# SAIIoT2020_AccelKart.net
KiCad netlist of a schematic drawn in EasyEDA
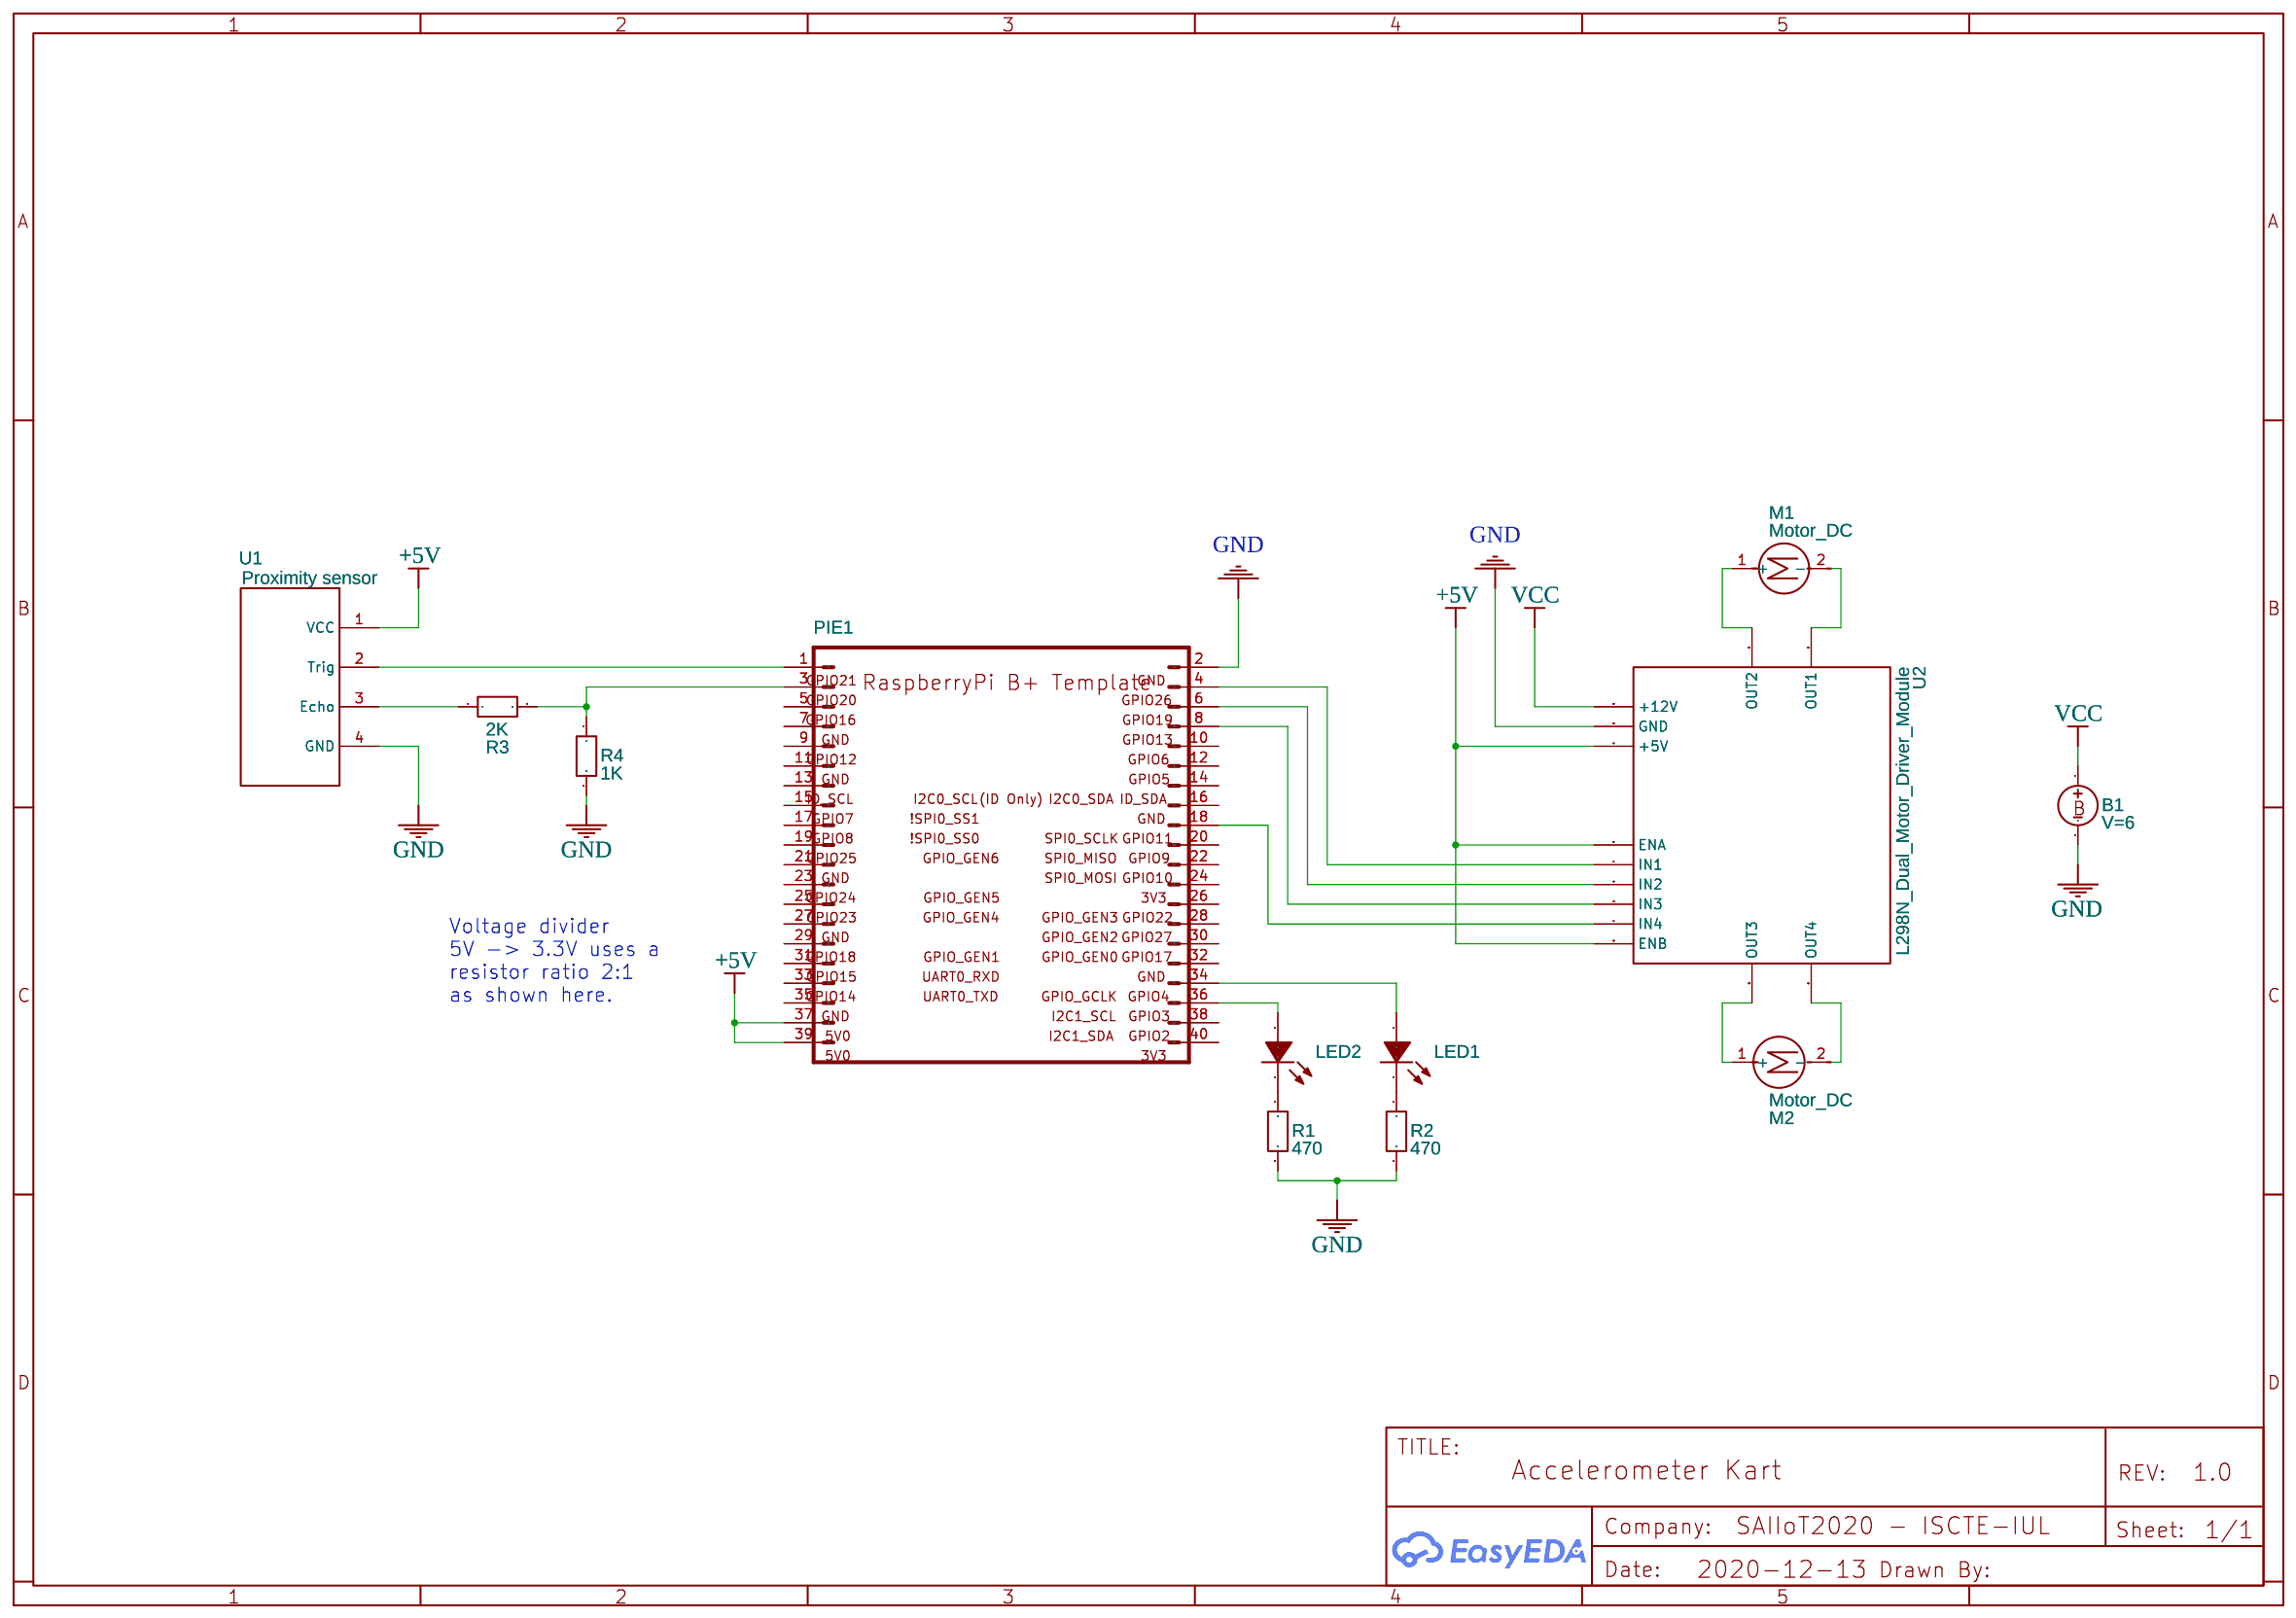
[diagram p0: Kart]
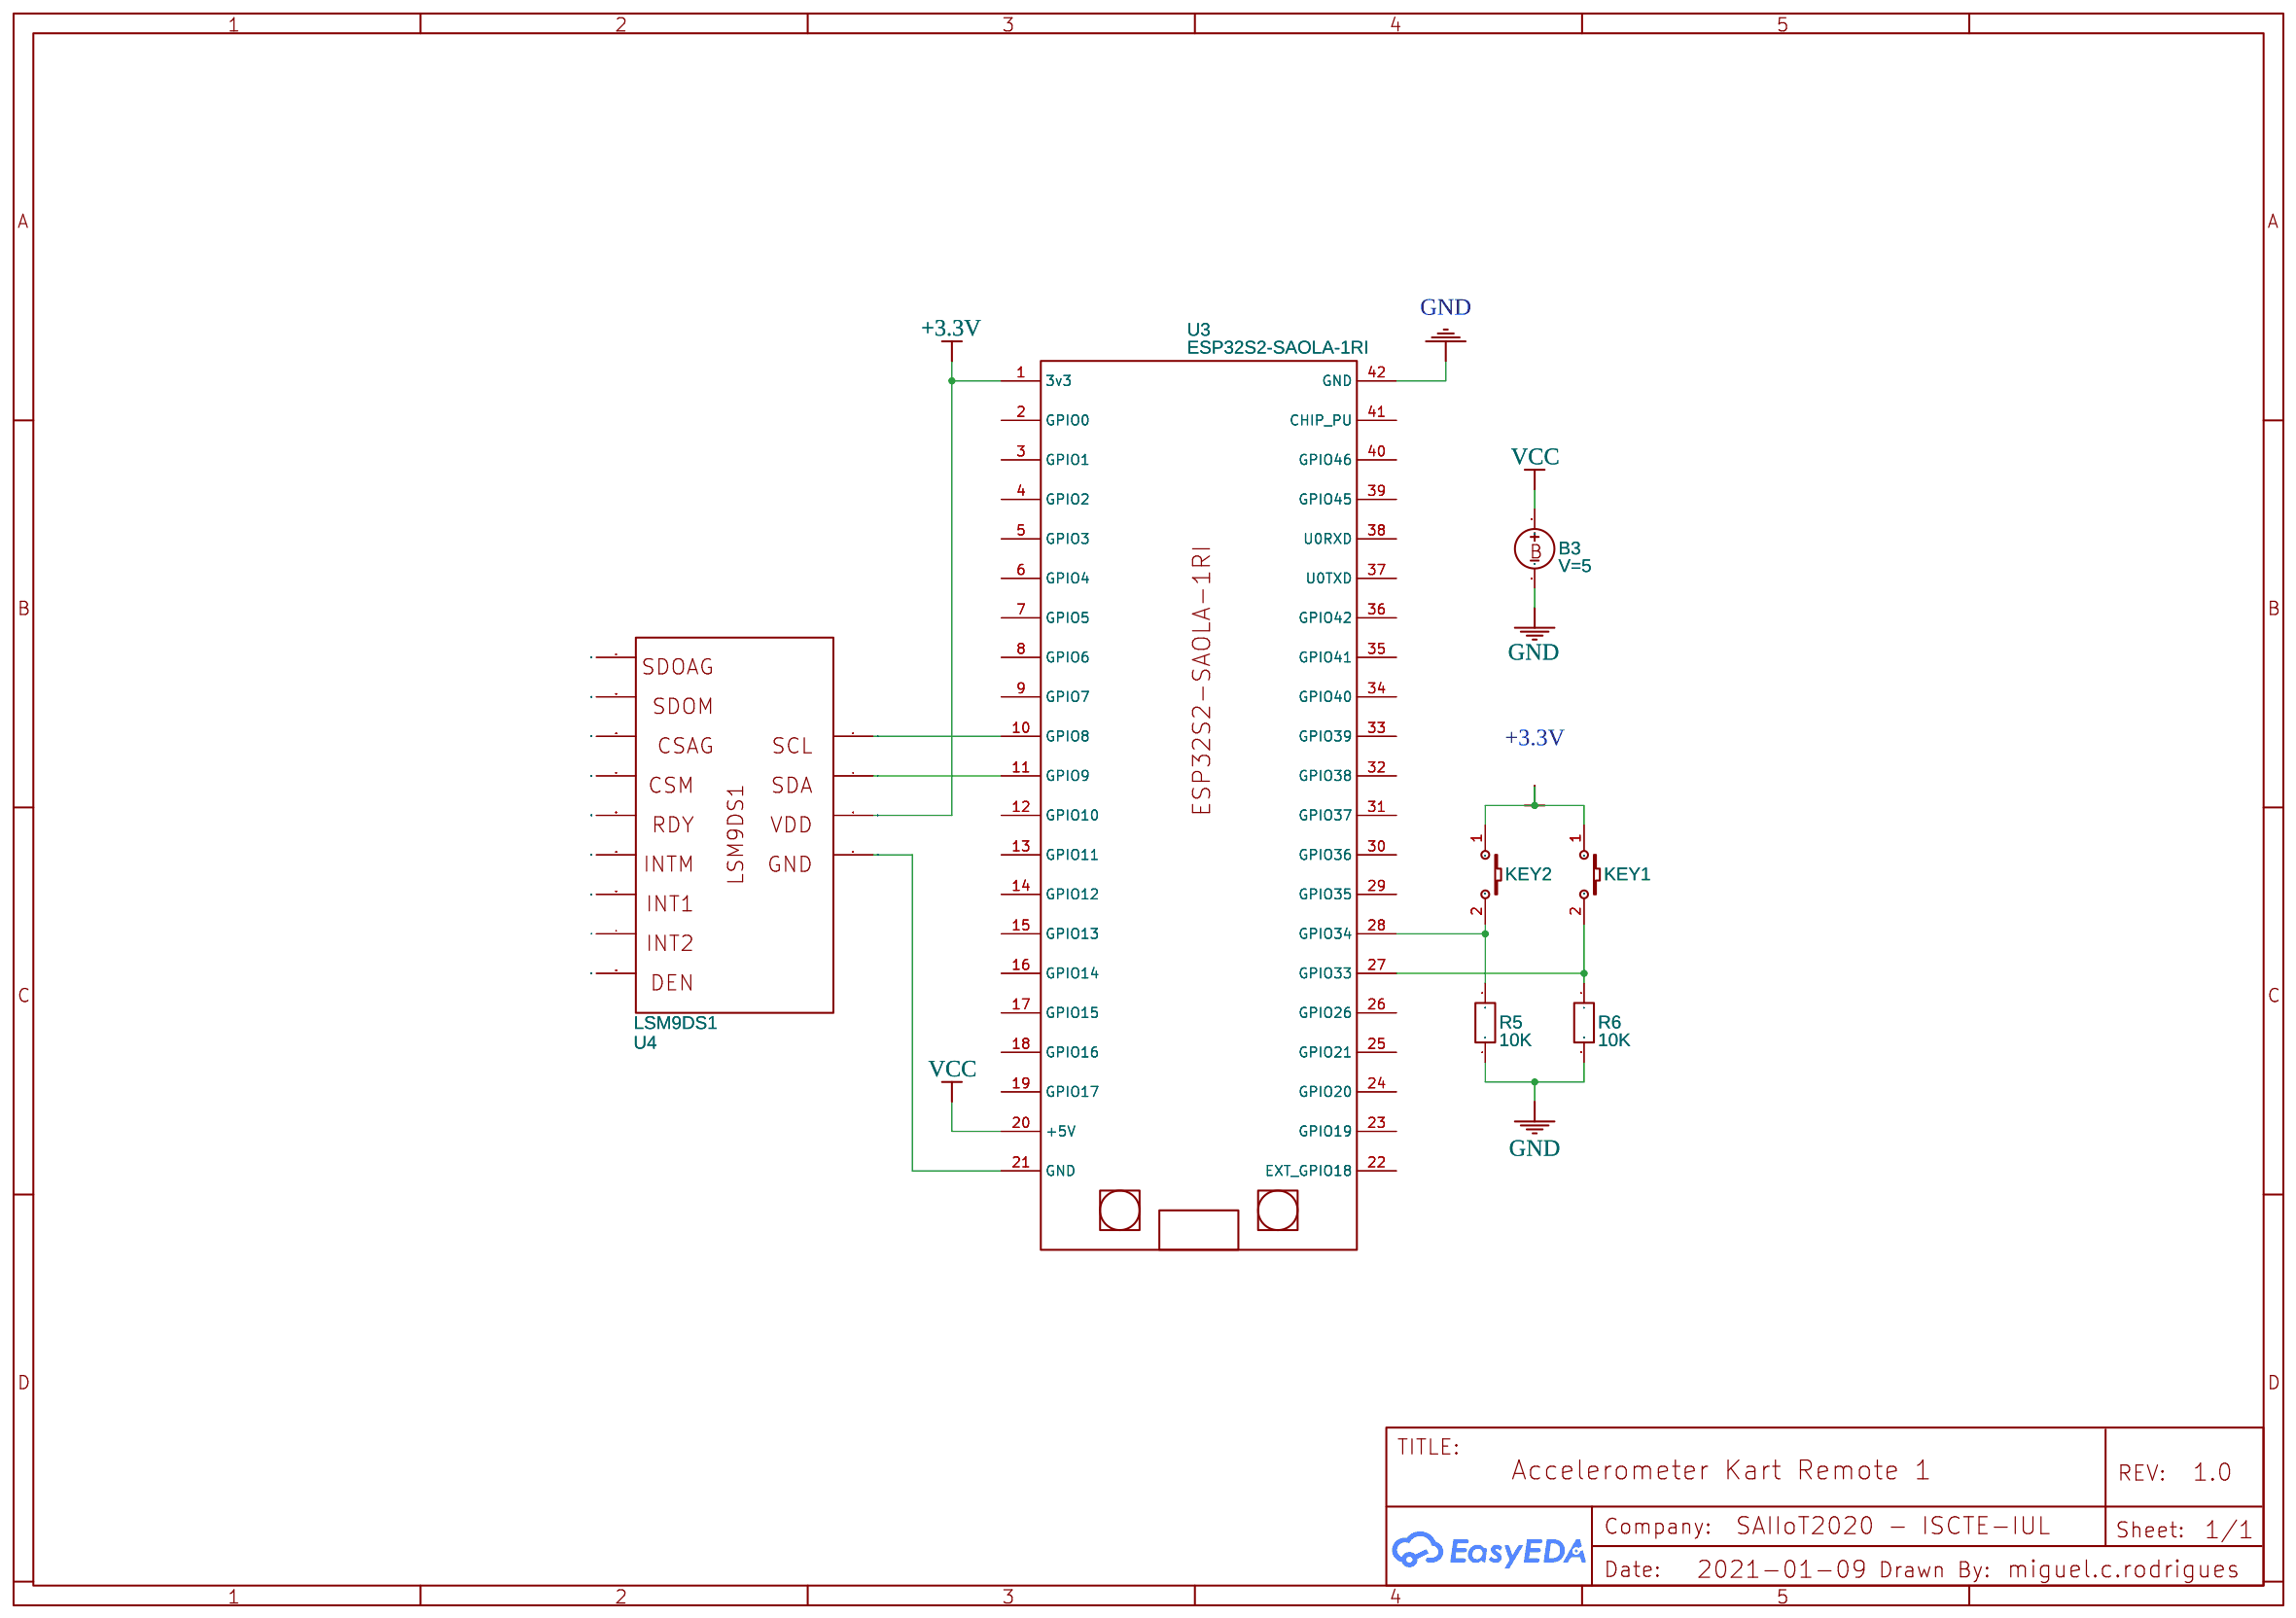
[diagram p1: Remote 1]
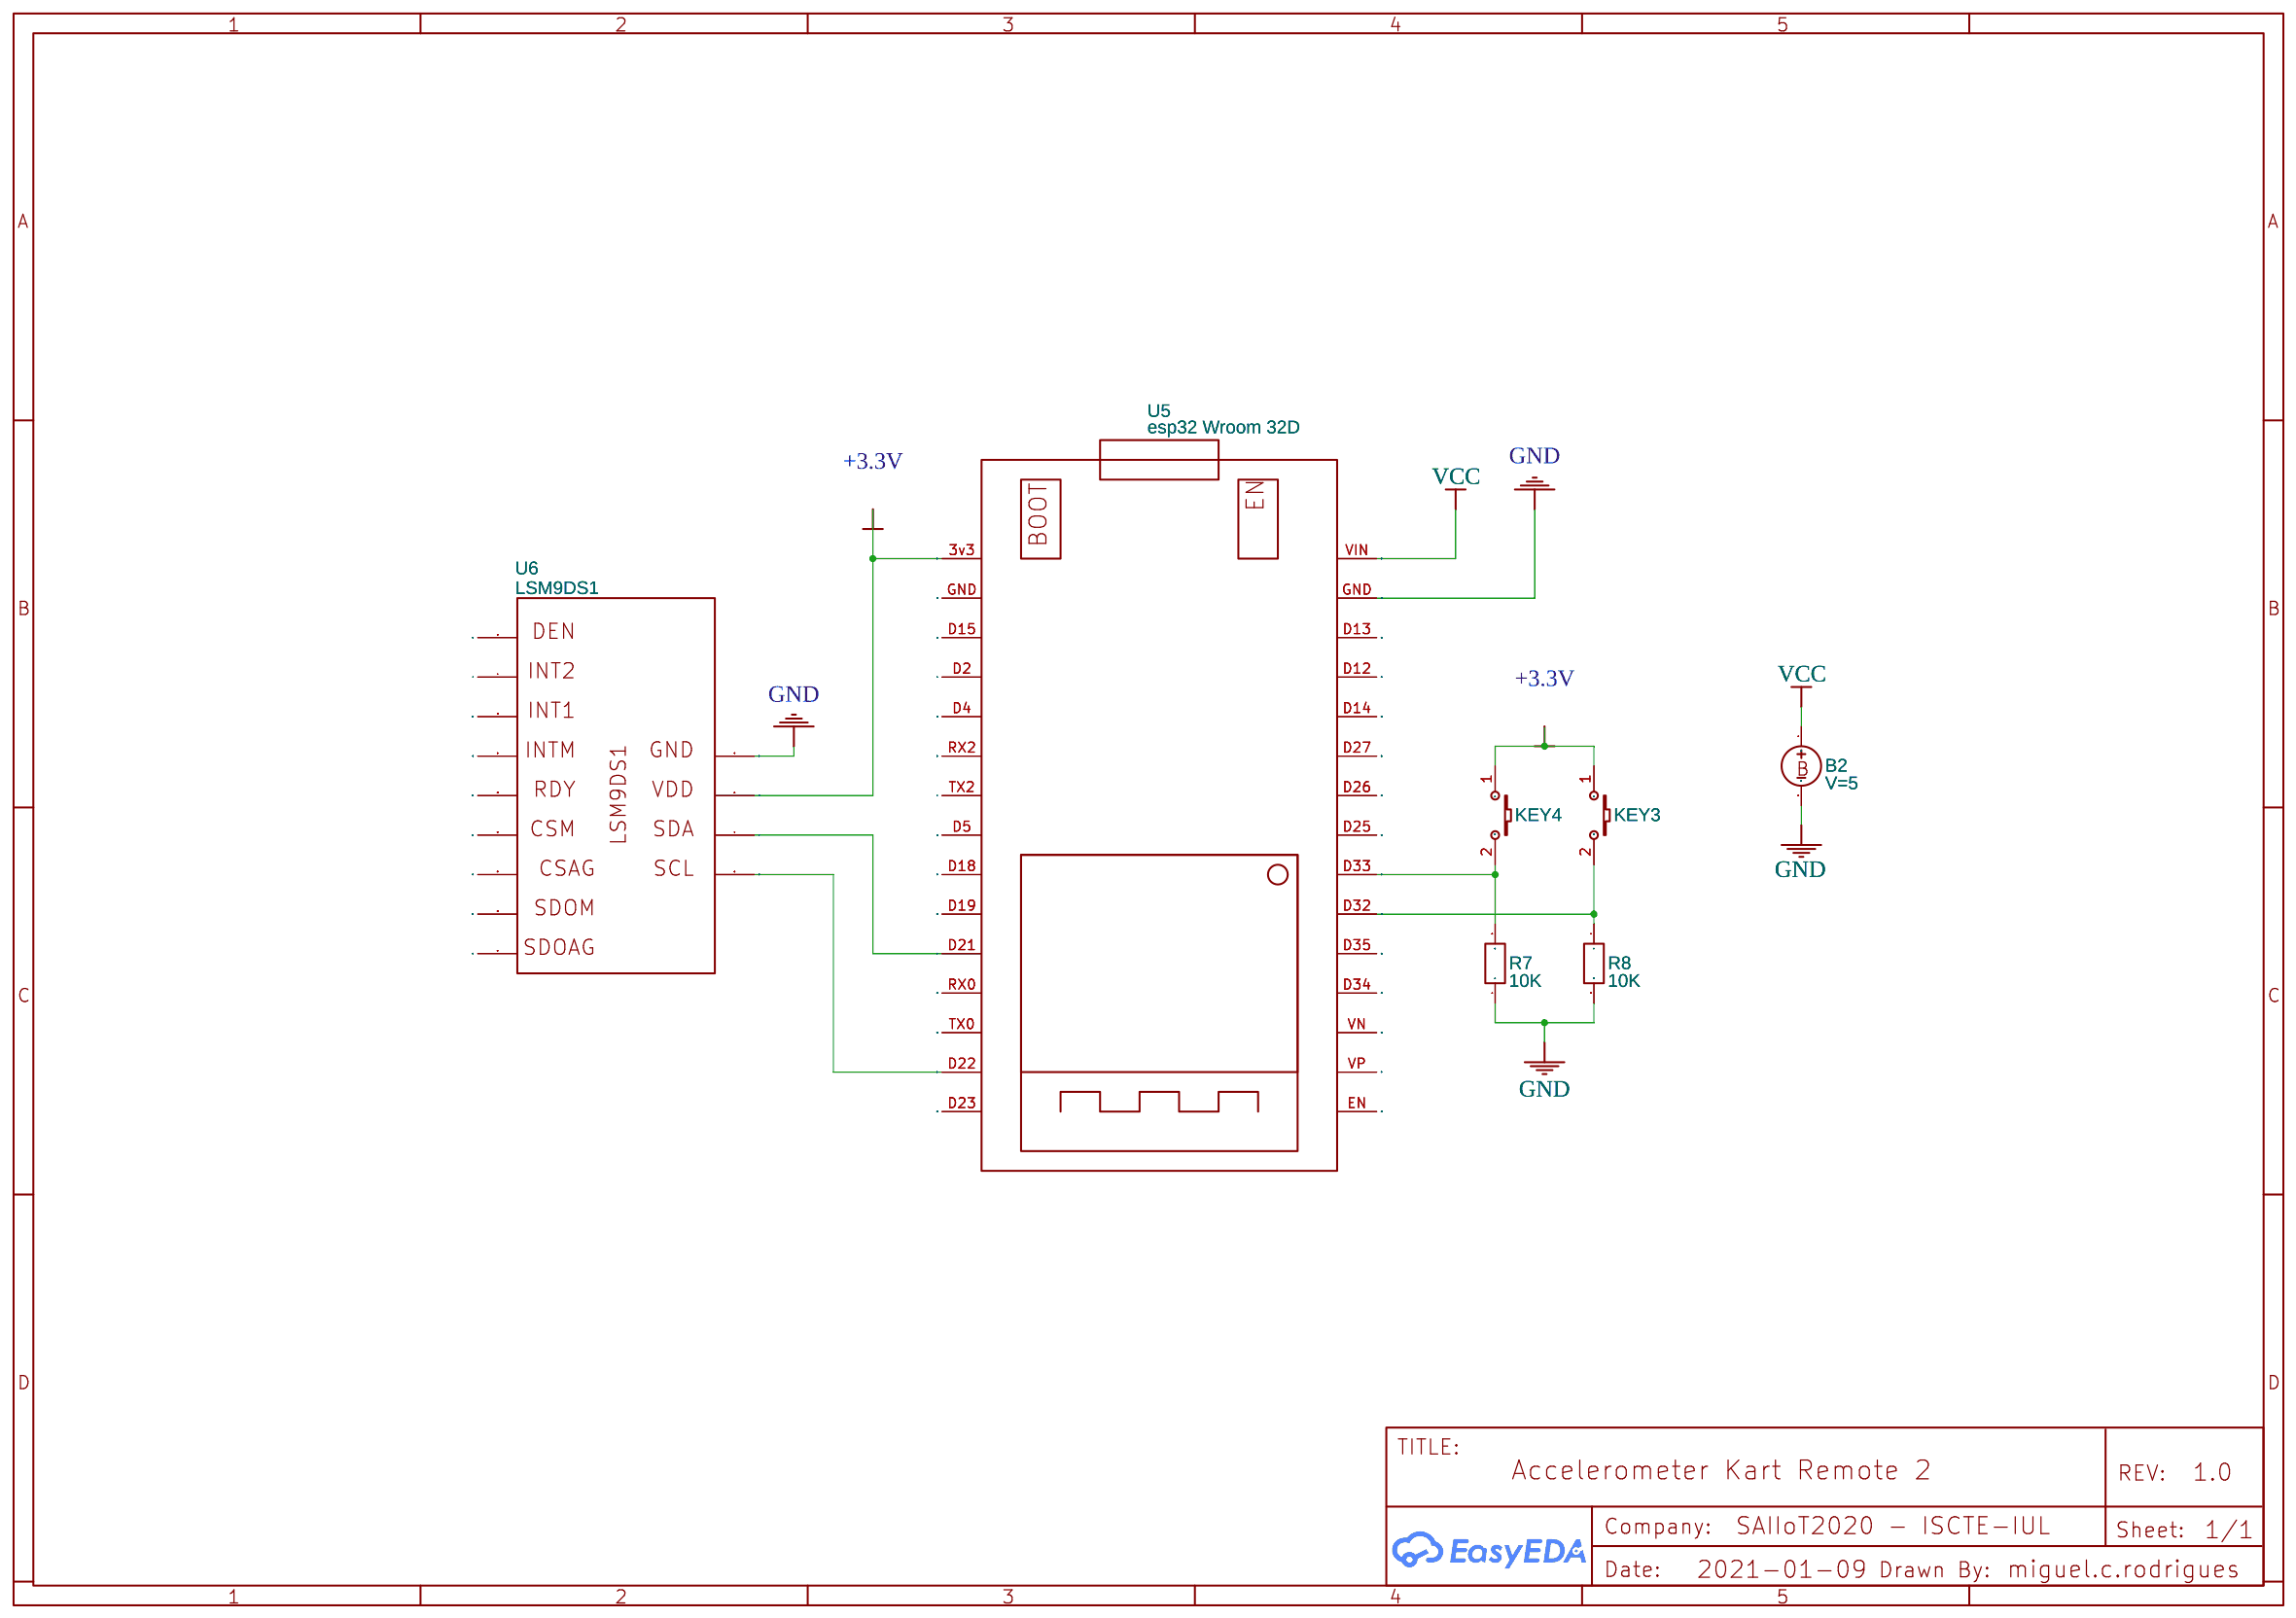
[diagram p2: Remote 2]

(export (version "E")
  (design (tool "Eeschema 10.0.6"))
  (components
    (comp (ref "B1") (value "V=6") (libsource (lib "") (part "BV_Behavioral_Source")))
    (comp (ref "LED1")
      (value "LED-0603_R")
      (fields
        (field (name "BOM_Manufacturer Part") "19-217/R6C-AL1M2VY/3T")
        (field (name "BOM_Supplier Part") "C72044")
      )
      (libsource (lib "") (part "LED-0603_R"))
    )
    (comp (ref "LED2")
      (value "LED-0603_R")
      (fields
        (field (name "BOM_Manufacturer Part") "19-217/R6C-AL1M2VY/3T")
        (field (name "BOM_Supplier Part") "C72044")
      )
      (libsource (lib "") (part "LED-0603_R"))
    )
    (comp (ref "M1") (value "Motor_DC") (libsource (lib "") (part "Motor_DC_1")))
    (comp (ref "M2") (value "Motor_DC") (libsource (lib "") (part "Motor_DC")))
    (comp (ref "PIE1") (value "PA_RASPI_BPLUS_BRD") (libsource (lib "") (part "PA_RASPI_BPLUS_BRD")))
    (comp (ref "R1") (value "470") (libsource (lib "") (part "R_0603_EU")))
    (comp (ref "R2") (value "470") (libsource (lib "") (part "R_0603_EU")))
    (comp (ref "R3") (value "2K") (libsource (lib "") (part "R_0603_EU_1")))
    (comp (ref "R4") (value "1K") (libsource (lib "") (part "R_0603_EU")))
    (comp (ref "U1")
      (value "Proximity sensor")
      (fields (field (name "BOM_Manufacturer Part") "HC-SR04"))
      (libsource (lib "") (part "Proximity sensor"))
    )
    (comp (ref "U2")
      (value "L298N_Dual_Motor_Driver_Module")
      (libsource (lib "") (part "L298N_Dual_Motor_Driver_Module"))
    )
    (comp (ref "B3") (value "V=5") (libsource (lib "") (part "BV_Behavioral_Source")))
    (comp (ref "KEY1")
      (value "K2-3.6×6.1_SMD")
      (fields
        (field (name "BOM_Manufacturer Part") "K2-1107ST-A4SW-06")
        (field (name "BOM_Supplier Part") "C118141")
      )
      (libsource (lib "") (part "K2-3.6×6.1_SMD"))
    )
    (comp (ref "KEY2")
      (value "K2-3.6×6.1_SMD")
      (fields
        (field (name "BOM_Manufacturer Part") "K2-1107ST-A4SW-06")
        (field (name "BOM_Supplier Part") "C118141")
      )
      (libsource (lib "") (part "K2-3.6×6.1_SMD"))
    )
    (comp (ref "R5") (value "10K") (libsource (lib "") (part "R_0603_EU")))
    (comp (ref "R6") (value "10K") (libsource (lib "") (part "R_0603_EU_1")))
    (comp (ref "U3")
      (value "ESP32S2-SAOLA-1RI")
      (fields (field (name "BOM_Manufacturer Part") "ESP32 DEV KIT"))
      (libsource (lib "") (part "ESP32S2-SAOLA-1RI"))
    )
    (comp (ref "U4") (value "LSM9DS1") (libsource (lib "") (part "LSM9DS1")))
    (comp (ref "B2") (value "V=5") (libsource (lib "") (part "BV_Behavioral_Source")))
    (comp (ref "KEY3")
      (value "K2-3.6×6.1_SMD")
      (fields
        (field (name "BOM_Manufacturer Part") "K2-1107ST-A4SW-06")
        (field (name "BOM_Supplier Part") "C118141")
      )
      (libsource (lib "") (part "K2-3.6×6.1_SMD"))
    )
    (comp (ref "KEY4")
      (value "K2-3.6×6.1_SMD")
      (fields
        (field (name "BOM_Manufacturer Part") "K2-1107ST-A4SW-06")
        (field (name "BOM_Supplier Part") "C118141")
      )
      (libsource (lib "") (part "K2-3.6×6.1_SMD"))
    )
    (comp (ref "R7") (value "10K") (libsource (lib "") (part "R_0603_EU_1")))
    (comp (ref "R8") (value "10K") (libsource (lib "") (part "R_0603_EU")))
    (comp (ref "U5") (value "esp32 Wroom 32D") (libsource (lib "") (part "esp32 Wroom 32D")))
    (comp (ref "U6") (value "LSM9DS1") (libsource (lib "") (part "LSM9DS1")))
  )
  (nets
    (net (code "1") (name "+3.3V") (class "Default")
      (node (ref "KEY1") (pin "1") (pinfunction "1_1") (pintype "unspecified"))
      (node (ref "KEY2") (pin "1") (pinfunction "1_1") (pintype "unspecified"))
      (node (ref "KEY3") (pin "1") (pinfunction "1_1") (pintype "unspecified"))
      (node (ref "KEY4") (pin "1") (pinfunction "1_1") (pintype "unspecified"))
      (node (ref "U3") (pin "1") (pinfunction "3v3_1") (pintype "passive"))
      (node (ref "U5") (pin "3v3") (pinfunction "31_3v3") (pintype "unspecified"))
      (node (ref "U6") (pin "3") (pinfunction "3_3") (pintype "unspecified"))
    )
    (net (code "2") (name "+5V") (class "Default")
      (node (ref "PIE1") (pin "37") (pinfunction "37_37") (pintype "unspecified"))
      (node (ref "PIE1") (pin "39") (pinfunction "39_39") (pintype "unspecified"))
      (node (ref "U1") (pin "1") (pinfunction "VCC_1") (pintype "unspecified"))
      (node (ref "U2") (pin "+5V") (pinfunction "+5V_+5V") (pintype "unspecified"))
      (node (ref "U2") (pin "ENA") (pinfunction "ENA_ENA") (pintype "unspecified"))
      (node (ref "U2") (pin "ENB") (pinfunction "ENB_ENB") (pintype "unspecified"))
    )
    (net (code "3") (name "GND") (class "Default")
      (node (ref "B1") (pin "2") (pinfunction "2_2") (pintype "unspecified"))
      (node (ref "B2") (pin "2") (pinfunction "2_2") (pintype "unspecified"))
      (node (ref "B3") (pin "2") (pinfunction "2_2") (pintype "unspecified"))
      (node (ref "PIE1") (pin "2") (pinfunction "2_2") (pintype "unspecified"))
      (node (ref "R1") (pin "2") (pinfunction "2_2") (pintype "unspecified"))
      (node (ref "R2") (pin "2") (pinfunction "2_2") (pintype "unspecified"))
      (node (ref "R4") (pin "2") (pinfunction "2_2") (pintype "unspecified"))
      (node (ref "R5") (pin "1") (pinfunction "1_1") (pintype "unspecified"))
      (node (ref "R6") (pin "2") (pinfunction "2_2") (pintype "unspecified"))
      (node (ref "R7") (pin "1") (pinfunction "1_1") (pintype "unspecified"))
      (node (ref "R8") (pin "2") (pinfunction "2_2") (pintype "unspecified"))
      (node (ref "U1") (pin "4") (pinfunction "GND_4") (pintype "unspecified"))
      (node (ref "U2") (pin "GND") (pinfunction "GND_GND") (pintype "unspecified"))
      (node (ref "U3") (pin "42") (pinfunction "GND_42") (pintype "passive"))
      (node (ref "U5") (pin "GND") (pinfunction "29_GND") (pintype "unspecified"))
      (node (ref "U6") (pin "2") (pinfunction "2_2") (pintype "unspecified"))
    )
    (net (code "4") (name "Net-(LED1-Pad1)") (class "Default")
      (node (ref "LED1") (pin "1") (pinfunction "1_1") (pintype "unspecified"))
      (node (ref "PIE1") (pin "34") (pinfunction "34_34") (pintype "unspecified"))
    )
    (net (code "5") (name "Net-(LED1-Pad2)") (class "Default")
      (node (ref "LED1") (pin "2") (pinfunction "2_2") (pintype "unspecified"))
      (node (ref "R2") (pin "1") (pinfunction "1_1") (pintype "unspecified"))
    )
    (net (code "6") (name "Net-(LED2-Pad1)") (class "Default")
      (node (ref "LED2") (pin "1") (pinfunction "1_1") (pintype "unspecified"))
      (node (ref "PIE1") (pin "36") (pinfunction "36_36") (pintype "unspecified"))
    )
    (net (code "7") (name "Net-(LED2-Pad2)") (class "Default")
      (node (ref "LED2") (pin "2") (pinfunction "2_2") (pintype "unspecified"))
      (node (ref "R1") (pin "1") (pinfunction "1_1") (pintype "unspecified"))
    )
    (net (code "8") (name "Net-(M1-+)") (class "Default")
      (node (ref "M1") (pin "1") (pinfunction "+_1") (pintype "unspecified"))
      (node (ref "U2") (pin "OUT2") (pinfunction "OUT2_OUT2") (pintype "unspecified"))
    )
    (net (code "9") (name "Net-(M1--)") (class "Default")
      (node (ref "M1") (pin "2") (pinfunction "-_2") (pintype "unspecified"))
      (node (ref "U2") (pin "OUT1") (pinfunction "OUT1_OUT1") (pintype "unspecified"))
    )
    (net (code "10") (name "Net-(M2-+)") (class "Default")
      (node (ref "M2") (pin "1") (pinfunction "+_1") (pintype "unspecified"))
      (node (ref "U2") (pin "OUT3") (pinfunction "OUT3_OUT3") (pintype "unspecified"))
    )
    (net (code "11") (name "Net-(M2--)") (class "Default")
      (node (ref "M2") (pin "2") (pinfunction "-_2") (pintype "unspecified"))
      (node (ref "U2") (pin "OUT4") (pinfunction "OUT4_OUT4") (pintype "unspecified"))
    )
    (net (code "12") (name "Net-(PIE1-Pad3)") (class "Default")
      (node (ref "PIE1") (pin "3") (pinfunction "3_3") (pintype "unspecified"))
      (node (ref "R3") (pin "2") (pinfunction "2_2") (pintype "unspecified"))
      (node (ref "R4") (pin "1") (pinfunction "1_1") (pintype "unspecified"))
    )
    (net (code "13") (name "Net-(PIE1-Pad4)") (class "Default")
      (node (ref "PIE1") (pin "4") (pinfunction "4_4") (pintype "unspecified"))
      (node (ref "U2") (pin "IN1") (pinfunction "IN1_IN1") (pintype "unspecified"))
    )
    (net (code "14") (name "Net-(PIE1-Pad6)") (class "Default")
      (node (ref "PIE1") (pin "6") (pinfunction "6_6") (pintype "unspecified"))
      (node (ref "U2") (pin "IN2") (pinfunction "IN2_IN2") (pintype "unspecified"))
    )
    (net (code "15") (name "Net-(PIE1-Pad8)") (class "Default")
      (node (ref "PIE1") (pin "8") (pinfunction "8_8") (pintype "unspecified"))
      (node (ref "U2") (pin "IN3") (pinfunction "IN3_IN3") (pintype "unspecified"))
    )
    (net (code "16") (name "Net-(PIE1-Pad18)") (class "Default")
      (node (ref "PIE1") (pin "18") (pinfunction "18_18") (pintype "unspecified"))
      (node (ref "U2") (pin "IN4") (pinfunction "IN4_IN4") (pintype "unspecified"))
    )
    (net (code "17") (name "Net-(U1-Echo)") (class "Default")
      (node (ref "R3") (pin "1") (pinfunction "1_1") (pintype "unspecified"))
      (node (ref "U1") (pin "3") (pinfunction "Echo_3") (pintype "unspecified"))
    )
    (net (code "18") (name "Net-(U1-Trig)") (class "Default")
      (node (ref "PIE1") (pin "1") (pinfunction "1_1") (pintype "unspecified"))
      (node (ref "U1") (pin "2") (pinfunction "Trig_2") (pintype "unspecified"))
    )
    (net (code "19") (name "Net-(U3-GPIO8)") (class "Default")
      (node (ref "U3") (pin "10") (pinfunction "GPIO8_10") (pintype "bidirectional"))
      (node (ref "U4") (pin "5") (pinfunction "5_5") (pintype "unspecified"))
    )
    (net (code "20") (name "Net-(U3-GPIO9)") (class "Default")
      (node (ref "U3") (pin "11") (pinfunction "GPIO9_11") (pintype "bidirectional"))
      (node (ref "U4") (pin "4") (pinfunction "4_4") (pintype "unspecified"))
    )
    (net (code "21") (name "Net-(U3-GPIO33)") (class "Default")
      (node (ref "KEY1") (pin "2") (pinfunction "2_2") (pintype "unspecified"))
      (node (ref "R6") (pin "1") (pinfunction "1_1") (pintype "unspecified"))
      (node (ref "U3") (pin "27") (pinfunction "GPIO33_27") (pintype "unspecified"))
    )
    (net (code "22") (name "Net-(U3-GPIO34)") (class "Default")
      (node (ref "KEY2") (pin "2") (pinfunction "2_2") (pintype "unspecified"))
      (node (ref "R5") (pin "2") (pinfunction "2_2") (pintype "unspecified"))
      (node (ref "U3") (pin "28") (pinfunction "GPIO34_28") (pintype "bidirectional"))
    )
    (net (code "23") (name "Net-(U5-11)") (class "Default")
      (node (ref "U5") (pin "D21") (pinfunction "11_D21") (pintype "unspecified"))
      (node (ref "U6") (pin "4") (pinfunction "4_4") (pintype "unspecified"))
    )
    (net (code "24") (name "Net-(U5-14)") (class "Default")
      (node (ref "U5") (pin "D22") (pinfunction "14_D22") (pintype "unspecified"))
      (node (ref "U6") (pin "5") (pinfunction "5_5") (pintype "unspecified"))
    )
    (net (code "25") (name "Net-(U5-21)") (class "Default")
      (node (ref "KEY3") (pin "2") (pinfunction "2_2") (pintype "unspecified"))
      (node (ref "R8") (pin "1") (pinfunction "1_1") (pintype "unspecified"))
      (node (ref "U5") (pin "D32") (pinfunction "21_D32") (pintype "unspecified"))
    )
    (net (code "26") (name "Net-(U5-22)") (class "Default")
      (node (ref "KEY4") (pin "2") (pinfunction "2_2") (pintype "unspecified"))
      (node (ref "R7") (pin "2") (pinfunction "2_2") (pintype "unspecified"))
      (node (ref "U5") (pin "D33") (pinfunction "22_D33") (pintype "unspecified"))
    )
    (net (code "27") (name "VCC") (class "Default")
      (node (ref "B1") (pin "1") (pinfunction "1_1") (pintype "unspecified"))
      (node (ref "B2") (pin "1") (pinfunction "1_1") (pintype "unspecified"))
      (node (ref "B3") (pin "1") (pinfunction "1_1") (pintype "unspecified"))
      (node (ref "U2") (pin "+12V") (pinfunction "+12V_+12V") (pintype "unspecified"))
      (node (ref "U3") (pin "20") (pinfunction "+5V_20") (pintype "unspecified"))
      (node (ref "U5") (pin "VIN") (pinfunction "30_VIN") (pintype "unspecified"))
    )
    (net (code "28") (name "unconnected-(PIE1-Pad5)") (class "Default")
      (node (ref "PIE1") (pin "5") (pinfunction "5_5") (pintype "unspecified"))
    )
    (net (code "29") (name "unconnected-(PIE1-Pad7)") (class "Default")
      (node (ref "PIE1") (pin "7") (pinfunction "7_7") (pintype "unspecified"))
    )
    (net (code "30") (name "unconnected-(PIE1-Pad9)") (class "Default")
      (node (ref "PIE1") (pin "9") (pinfunction "9_9") (pintype "unspecified"))
    )
    (net (code "31") (name "unconnected-(PIE1-Pad10)") (class "Default")
      (node (ref "PIE1") (pin "10") (pinfunction "10_10") (pintype "unspecified"))
    )
    (net (code "32") (name "unconnected-(PIE1-Pad11)") (class "Default")
      (node (ref "PIE1") (pin "11") (pinfunction "11_11") (pintype "unspecified"))
    )
    (net (code "33") (name "unconnected-(PIE1-Pad12)") (class "Default")
      (node (ref "PIE1") (pin "12") (pinfunction "12_12") (pintype "unspecified"))
    )
    (net (code "34") (name "unconnected-(PIE1-Pad13)") (class "Default")
      (node (ref "PIE1") (pin "13") (pinfunction "13_13") (pintype "unspecified"))
    )
    (net (code "35") (name "unconnected-(PIE1-Pad14)") (class "Default")
      (node (ref "PIE1") (pin "14") (pinfunction "14_14") (pintype "unspecified"))
    )
    (net (code "36") (name "unconnected-(PIE1-Pad15)") (class "Default")
      (node (ref "PIE1") (pin "15") (pinfunction "15_15") (pintype "unspecified"))
    )
    (net (code "37") (name "unconnected-(PIE1-Pad16)") (class "Default")
      (node (ref "PIE1") (pin "16") (pinfunction "16_16") (pintype "unspecified"))
    )
    (net (code "38") (name "unconnected-(PIE1-Pad17)") (class "Default")
      (node (ref "PIE1") (pin "17") (pinfunction "17_17") (pintype "unspecified"))
    )
    (net (code "39") (name "unconnected-(PIE1-Pad19)") (class "Default")
      (node (ref "PIE1") (pin "19") (pinfunction "19_19") (pintype "unspecified"))
    )
    (net (code "40") (name "unconnected-(PIE1-Pad20)") (class "Default")
      (node (ref "PIE1") (pin "20") (pinfunction "20_20") (pintype "unspecified"))
    )
    (net (code "41") (name "unconnected-(PIE1-Pad21)") (class "Default")
      (node (ref "PIE1") (pin "21") (pinfunction "21_21") (pintype "unspecified"))
    )
    (net (code "42") (name "unconnected-(PIE1-Pad22)") (class "Default")
      (node (ref "PIE1") (pin "22") (pinfunction "22_22") (pintype "unspecified"))
    )
    (net (code "43") (name "unconnected-(PIE1-Pad23)") (class "Default")
      (node (ref "PIE1") (pin "23") (pinfunction "23_23") (pintype "unspecified"))
    )
    (net (code "44") (name "unconnected-(PIE1-Pad24)") (class "Default")
      (node (ref "PIE1") (pin "24") (pinfunction "24_24") (pintype "unspecified"))
    )
    (net (code "45") (name "unconnected-(PIE1-Pad25)") (class "Default")
      (node (ref "PIE1") (pin "25") (pinfunction "25_25") (pintype "unspecified"))
    )
    (net (code "46") (name "unconnected-(PIE1-Pad26)") (class "Default")
      (node (ref "PIE1") (pin "26") (pinfunction "26_26") (pintype "unspecified"))
    )
    (net (code "47") (name "unconnected-(PIE1-Pad27)") (class "Default")
      (node (ref "PIE1") (pin "27") (pinfunction "27_27") (pintype "unspecified"))
    )
    (net (code "48") (name "unconnected-(PIE1-Pad28)") (class "Default")
      (node (ref "PIE1") (pin "28") (pinfunction "28_28") (pintype "unspecified"))
    )
    (net (code "49") (name "unconnected-(PIE1-Pad29)") (class "Default")
      (node (ref "PIE1") (pin "29") (pinfunction "29_29") (pintype "unspecified"))
    )
    (net (code "50") (name "unconnected-(PIE1-Pad30)") (class "Default")
      (node (ref "PIE1") (pin "30") (pinfunction "30_30") (pintype "unspecified"))
    )
    (net (code "51") (name "unconnected-(PIE1-Pad31)") (class "Default")
      (node (ref "PIE1") (pin "31") (pinfunction "31_31") (pintype "unspecified"))
    )
    (net (code "52") (name "unconnected-(PIE1-Pad32)") (class "Default")
      (node (ref "PIE1") (pin "32") (pinfunction "32_32") (pintype "unspecified"))
    )
    (net (code "53") (name "unconnected-(PIE1-Pad33)") (class "Default")
      (node (ref "PIE1") (pin "33") (pinfunction "33_33") (pintype "unspecified"))
    )
    (net (code "54") (name "unconnected-(PIE1-Pad35)") (class "Default")
      (node (ref "PIE1") (pin "35") (pinfunction "35_35") (pintype "unspecified"))
    )
    (net (code "55") (name "unconnected-(PIE1-Pad38)") (class "Default")
      (node (ref "PIE1") (pin "38") (pinfunction "38_38") (pintype "unspecified"))
    )
    (net (code "56") (name "unconnected-(PIE1-Pad40)") (class "Default")
      (node (ref "PIE1") (pin "40") (pinfunction "40_40") (pintype "unspecified"))
    )
    (net (code "57") (name "unconnected-(U3-CHIP_PU-Pad41)") (class "Default")
      (node (ref "U3") (pin "41") (pinfunction "CHIP_PU_41") (pintype "passive"))
    )
    (net (code "58") (name "unconnected-(U3-EXT_GPIO18-Pad22)") (class "Default")
      (node (ref "U3") (pin "22") (pinfunction "EXT_GPIO18_22") (pintype "unspecified"))
    )
    (net (code "59") (name "unconnected-(U3-GND-Pad21)") (class "Default")
      (node (ref "U3") (pin "21") (pinfunction "GND_21") (pintype "unspecified"))
    )
    (net (code "60") (name "unconnected-(U3-GPIO0-Pad2)") (class "Default")
      (node (ref "U3") (pin "2") (pinfunction "GPIO0_2") (pintype "passive"))
    )
    (net (code "61") (name "unconnected-(U3-GPIO1-Pad3)") (class "Default")
      (node (ref "U3") (pin "3") (pinfunction "GPIO1_3") (pintype "bidirectional"))
    )
    (net (code "62") (name "unconnected-(U3-GPIO2-Pad4)") (class "Default")
      (node (ref "U3") (pin "4") (pinfunction "GPIO2_4") (pintype "bidirectional"))
    )
    (net (code "63") (name "unconnected-(U3-GPIO3-Pad5)") (class "Default")
      (node (ref "U3") (pin "5") (pinfunction "GPIO3_5") (pintype "bidirectional"))
    )
    (net (code "64") (name "unconnected-(U3-GPIO4-Pad6)") (class "Default")
      (node (ref "U3") (pin "6") (pinfunction "GPIO4_6") (pintype "bidirectional"))
    )
    (net (code "65") (name "unconnected-(U3-GPIO5-Pad7)") (class "Default")
      (node (ref "U3") (pin "7") (pinfunction "GPIO5_7") (pintype "bidirectional"))
    )
    (net (code "66") (name "unconnected-(U3-GPIO6-Pad8)") (class "Default")
      (node (ref "U3") (pin "8") (pinfunction "GPIO6_8") (pintype "unspecified"))
    )
    (net (code "67") (name "unconnected-(U3-GPIO7-Pad9)") (class "Default")
      (node (ref "U3") (pin "9") (pinfunction "GPIO7_9") (pintype "unspecified"))
    )
    (net (code "68") (name "unconnected-(U3-GPIO10-Pad12)") (class "Default")
      (node (ref "U3") (pin "12") (pinfunction "GPIO10_12") (pintype "bidirectional"))
    )
    (net (code "69") (name "unconnected-(U3-GPIO11-Pad13)") (class "Default")
      (node (ref "U3") (pin "13") (pinfunction "GPIO11_13") (pintype "bidirectional"))
    )
    (net (code "70") (name "unconnected-(U3-GPIO12-Pad14)") (class "Default")
      (node (ref "U3") (pin "14") (pinfunction "GPIO12_14") (pintype "bidirectional"))
    )
    (net (code "71") (name "unconnected-(U3-GPIO13-Pad15)") (class "Default")
      (node (ref "U3") (pin "15") (pinfunction "GPIO13_15") (pintype "bidirectional"))
    )
    (net (code "72") (name "unconnected-(U3-GPIO14-Pad16)") (class "Default")
      (node (ref "U3") (pin "16") (pinfunction "GPIO14_16") (pintype "unspecified"))
    )
    (net (code "73") (name "unconnected-(U3-GPIO15-Pad17)") (class "Default")
      (node (ref "U3") (pin "17") (pinfunction "GPIO15_17") (pintype "unspecified"))
    )
    (net (code "74") (name "unconnected-(U3-GPIO16-Pad18)") (class "Default")
      (node (ref "U3") (pin "18") (pinfunction "GPIO16_18") (pintype "unspecified"))
    )
    (net (code "75") (name "unconnected-(U3-GPIO17-Pad19)") (class "Default")
      (node (ref "U3") (pin "19") (pinfunction "GPIO17_19") (pintype "unspecified"))
    )
    (net (code "76") (name "unconnected-(U3-GPIO19-Pad23)") (class "Default")
      (node (ref "U3") (pin "23") (pinfunction "GPIO19_23") (pintype "unspecified"))
    )
    (net (code "77") (name "unconnected-(U3-GPIO20-Pad24)") (class "Default")
      (node (ref "U3") (pin "24") (pinfunction "GPIO20_24") (pintype "unspecified"))
    )
    (net (code "78") (name "unconnected-(U3-GPIO21-Pad25)") (class "Default")
      (node (ref "U3") (pin "25") (pinfunction "GPIO21_25") (pintype "unspecified"))
    )
    (net (code "79") (name "unconnected-(U3-GPIO26-Pad26)") (class "Default")
      (node (ref "U3") (pin "26") (pinfunction "GPIO26_26") (pintype "unspecified"))
    )
    (net (code "80") (name "unconnected-(U3-GPIO35-Pad29)") (class "Default")
      (node (ref "U3") (pin "29") (pinfunction "GPIO35_29") (pintype "passive"))
    )
    (net (code "81") (name "unconnected-(U3-GPIO36-Pad30)") (class "Default")
      (node (ref "U3") (pin "30") (pinfunction "GPIO36_30") (pintype "passive"))
    )
    (net (code "82") (name "unconnected-(U3-GPIO37-Pad31)") (class "Default")
      (node (ref "U3") (pin "31") (pinfunction "GPIO37_31") (pintype "passive"))
    )
    (net (code "83") (name "unconnected-(U3-GPIO38-Pad32)") (class "Default")
      (node (ref "U3") (pin "32") (pinfunction "GPIO38_32") (pintype "passive"))
    )
    (net (code "84") (name "unconnected-(U3-GPIO39-Pad33)") (class "Default")
      (node (ref "U3") (pin "33") (pinfunction "GPIO39_33") (pintype "passive"))
    )
    (net (code "85") (name "unconnected-(U3-GPIO40-Pad34)") (class "Default")
      (node (ref "U3") (pin "34") (pinfunction "GPIO40_34") (pintype "passive"))
    )
    (net (code "86") (name "unconnected-(U3-GPIO41-Pad35)") (class "Default")
      (node (ref "U3") (pin "35") (pinfunction "GPIO41_35") (pintype "passive"))
    )
    (net (code "87") (name "unconnected-(U3-GPIO42-Pad36)") (class "Default")
      (node (ref "U3") (pin "36") (pinfunction "GPIO42_36") (pintype "passive"))
    )
    (net (code "88") (name "unconnected-(U3-GPIO45-Pad39)") (class "Default")
      (node (ref "U3") (pin "39") (pinfunction "GPIO45_39") (pintype "passive"))
    )
    (net (code "89") (name "unconnected-(U3-GPIO46-Pad40)") (class "Default")
      (node (ref "U3") (pin "40") (pinfunction "GPIO46_40") (pintype "passive"))
    )
    (net (code "90") (name "unconnected-(U3-U0RXD-Pad38)") (class "Default")
      (node (ref "U3") (pin "38") (pinfunction "U0RXD_38") (pintype "passive"))
    )
    (net (code "91") (name "unconnected-(U3-U0TXD-Pad37)") (class "Default")
      (node (ref "U3") (pin "37") (pinfunction "U0TXD_37") (pintype "passive"))
    )
    (net (code "92") (name "unconnected-(U4-Pad2)") (class "Default")
      (node (ref "U4") (pin "2") (pinfunction "2_2") (pintype "unspecified"))
    )
    (net (code "93") (name "unconnected-(U4-Pad3)") (class "Default")
      (node (ref "U4") (pin "3") (pinfunction "3_3") (pintype "unspecified"))
    )
    (net (code "94") (name "unconnected-(U4-Pad6)") (class "Default")
      (node (ref "U4") (pin "6") (pinfunction "6_6") (pintype "unspecified"))
    )
    (net (code "95") (name "unconnected-(U4-Pad7)") (class "Default")
      (node (ref "U4") (pin "7") (pinfunction "7_7") (pintype "unspecified"))
    )
    (net (code "96") (name "unconnected-(U4-Pad8)") (class "Default")
      (node (ref "U4") (pin "8") (pinfunction "8_8") (pintype "unspecified"))
    )
    (net (code "97") (name "unconnected-(U4-Pad9)") (class "Default")
      (node (ref "U4") (pin "9") (pinfunction "9_9") (pintype "unspecified"))
    )
    (net (code "98") (name "unconnected-(U4-Pad10)") (class "Default")
      (node (ref "U4") (pin "10") (pinfunction "10_10") (pintype "unspecified"))
    )
    (net (code "99") (name "unconnected-(U4-Pad11)") (class "Default")
      (node (ref "U4") (pin "11") (pinfunction "11_11") (pintype "unspecified"))
    )
    (net (code "100") (name "unconnected-(U4-Pad12)") (class "Default")
      (node (ref "U4") (pin "12") (pinfunction "12_12") (pintype "unspecified"))
    )
    (net (code "101") (name "unconnected-(U4-Pad13)") (class "Default")
      (node (ref "U4") (pin "13") (pinfunction "13_13") (pintype "unspecified"))
    )
    (net (code "102") (name "unconnected-(U4-Pad14)") (class "Default")
      (node (ref "U4") (pin "14") (pinfunction "14_14") (pintype "unspecified"))
    )
    (net (code "103") (name "unconnected-(U5-2-PadGND)") (class "Default")
      (node (ref "U5") (pin "GND") (pinfunction "2_GND") (pintype "unspecified"))
    )
    (net (code "104") (name "unconnected-(U5-3-PadD15)") (class "Default")
      (node (ref "U5") (pin "D15") (pinfunction "3_D15") (pintype "unspecified"))
    )
    (net (code "105") (name "unconnected-(U5-4-PadD2)") (class "Default")
      (node (ref "U5") (pin "D2") (pinfunction "4_D2") (pintype "unspecified"))
    )
    (net (code "106") (name "unconnected-(U5-5-PadD4)") (class "Default")
      (node (ref "U5") (pin "D4") (pinfunction "5_D4") (pintype "unspecified"))
    )
    (net (code "107") (name "unconnected-(U5-6-PadRX2)") (class "Default")
      (node (ref "U5") (pin "RX2") (pinfunction "6_RX2") (pintype "unspecified"))
    )
    (net (code "108") (name "unconnected-(U5-7-PadTX2)") (class "Default")
      (node (ref "U5") (pin "TX2") (pinfunction "7_TX2") (pintype "unspecified"))
    )
    (net (code "109") (name "unconnected-(U5-8-PadD5)") (class "Default")
      (node (ref "U5") (pin "D5") (pinfunction "8_D5") (pintype "unspecified"))
    )
    (net (code "110") (name "unconnected-(U5-9-PadD18)") (class "Default")
      (node (ref "U5") (pin "D18") (pinfunction "9_D18") (pintype "unspecified"))
    )
    (net (code "111") (name "unconnected-(U5-10-PadD19)") (class "Default")
      (node (ref "U5") (pin "D19") (pinfunction "10_D19") (pintype "unspecified"))
    )
    (net (code "112") (name "unconnected-(U5-12-PadRX0)") (class "Default")
      (node (ref "U5") (pin "RX0") (pinfunction "12_RX0") (pintype "unspecified"))
    )
    (net (code "113") (name "unconnected-(U5-13-PadTX0)") (class "Default")
      (node (ref "U5") (pin "TX0") (pinfunction "13_TX0") (pintype "unspecified"))
    )
    (net (code "114") (name "unconnected-(U5-15-PadD23)") (class "Default")
      (node (ref "U5") (pin "D23") (pinfunction "15_D23") (pintype "unspecified"))
    )
    (net (code "115") (name "unconnected-(U5-16-PadEN)") (class "Default")
      (node (ref "U5") (pin "EN") (pinfunction "16_EN") (pintype "unspecified"))
    )
    (net (code "116") (name "unconnected-(U5-17-PadVP)") (class "Default")
      (node (ref "U5") (pin "VP") (pinfunction "17_VP") (pintype "unspecified"))
    )
    (net (code "117") (name "unconnected-(U5-18-PadVN)") (class "Default")
      (node (ref "U5") (pin "VN") (pinfunction "18_VN") (pintype "unspecified"))
    )
    (net (code "118") (name "unconnected-(U5-19-PadD34)") (class "Default")
      (node (ref "U5") (pin "D34") (pinfunction "19_D34") (pintype "unspecified"))
    )
    (net (code "119") (name "unconnected-(U5-20-PadD35)") (class "Default")
      (node (ref "U5") (pin "D35") (pinfunction "20_D35") (pintype "unspecified"))
    )
    (net (code "120") (name "unconnected-(U5-23-PadD25)") (class "Default")
      (node (ref "U5") (pin "D25") (pinfunction "23_D25") (pintype "unspecified"))
    )
    (net (code "121") (name "unconnected-(U5-24-PadD26)") (class "Default")
      (node (ref "U5") (pin "D26") (pinfunction "24_D26") (pintype "unspecified"))
    )
    (net (code "122") (name "unconnected-(U5-25-PadD27)") (class "Default")
      (node (ref "U5") (pin "D27") (pinfunction "25_D27") (pintype "unspecified"))
    )
    (net (code "123") (name "unconnected-(U5-26-PadD14)") (class "Default")
      (node (ref "U5") (pin "D14") (pinfunction "26_D14") (pintype "unspecified"))
    )
    (net (code "124") (name "unconnected-(U5-27-PadD12)") (class "Default")
      (node (ref "U5") (pin "D12") (pinfunction "27_D12") (pintype "unspecified"))
    )
    (net (code "125") (name "unconnected-(U5-28-PadD13)") (class "Default")
      (node (ref "U5") (pin "D13") (pinfunction "28_D13") (pintype "unspecified"))
    )
    (net (code "126") (name "unconnected-(U6-Pad6)") (class "Default")
      (node (ref "U6") (pin "6") (pinfunction "6_6") (pintype "unspecified"))
    )
    (net (code "127") (name "unconnected-(U6-Pad7)") (class "Default")
      (node (ref "U6") (pin "7") (pinfunction "7_7") (pintype "unspecified"))
    )
    (net (code "128") (name "unconnected-(U6-Pad8)") (class "Default")
      (node (ref "U6") (pin "8") (pinfunction "8_8") (pintype "unspecified"))
    )
    (net (code "129") (name "unconnected-(U6-Pad9)") (class "Default")
      (node (ref "U6") (pin "9") (pinfunction "9_9") (pintype "unspecified"))
    )
    (net (code "130") (name "unconnected-(U6-Pad10)") (class "Default")
      (node (ref "U6") (pin "10") (pinfunction "10_10") (pintype "unspecified"))
    )
    (net (code "131") (name "unconnected-(U6-Pad11)") (class "Default")
      (node (ref "U6") (pin "11") (pinfunction "11_11") (pintype "unspecified"))
    )
    (net (code "132") (name "unconnected-(U6-Pad12)") (class "Default")
      (node (ref "U6") (pin "12") (pinfunction "12_12") (pintype "unspecified"))
    )
    (net (code "133") (name "unconnected-(U6-Pad13)") (class "Default")
      (node (ref "U6") (pin "13") (pinfunction "13_13") (pintype "unspecified"))
    )
    (net (code "134") (name "unconnected-(U6-Pad14)") (class "Default")
      (node (ref "U6") (pin "14") (pinfunction "14_14") (pintype "unspecified"))
    )
  )
)
